# aw_201_clock.net
KiCad netlist of a schematic drawn in EAGLE
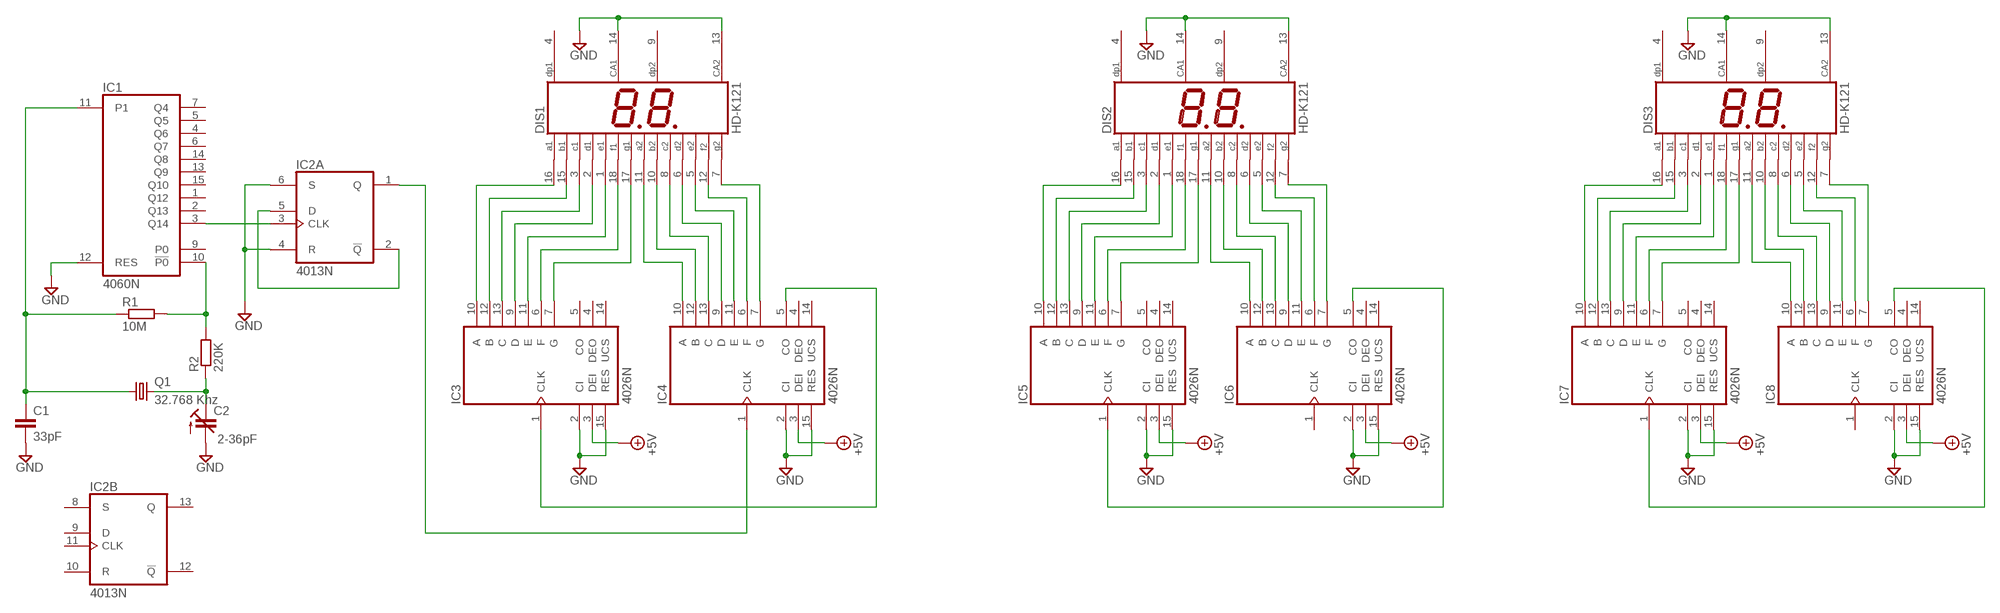
[diagram p0: schematic, sheet 1]

(export (version "E")
  (design (tool "Eeschema 10.0.6"))
  (components
    (comp (ref "C1")
      (value "33pF")
      (footprint "eagle-import:C050-024X044")
      (libsource (lib "eagle-import") (part "C-EU050-024X044"))
    )
    (comp (ref "C2")
      (value "2-36pF")
      (footprint "eagle-import:CTRIM3050.504")
      (libsource (lib "eagle-import") (part "C-TRIMM3050.504"))
    )
    (comp (ref "DIS1")
      (value "HD-K121")
      (footprint "eagle-import:HDSP-R")
      (libsource (lib "eagle-import") (part "HD-K121"))
    )
    (comp (ref "DIS2")
      (value "HD-K121")
      (footprint "eagle-import:HDSP-R")
      (libsource (lib "eagle-import") (part "HD-K121"))
    )
    (comp (ref "DIS3")
      (value "HD-K121")
      (footprint "eagle-import:HDSP-R")
      (libsource (lib "eagle-import") (part "HD-K121"))
    )
    (comp (ref "IC1")
      (value "4060N")
      (footprint "eagle-import:DIL16")
      (libsource (lib "eagle-import") (part "4060N"))
    )
    (comp (ref "IC2")
      (value "4013N")
      (footprint "eagle-import:DIL14")
      (libsource (lib "eagle-import") (part "4013N"))
    )
    (comp (ref "IC3")
      (value "4026N")
      (footprint "eagle-import:DIL16")
      (libsource (lib "eagle-import") (part "4026N"))
    )
    (comp (ref "IC4")
      (value "4026N")
      (footprint "eagle-import:DIL16")
      (libsource (lib "eagle-import") (part "4026N"))
    )
    (comp (ref "IC5")
      (value "4026N")
      (footprint "eagle-import:DIL16")
      (libsource (lib "eagle-import") (part "4026N"))
    )
    (comp (ref "IC6")
      (value "4026N")
      (footprint "eagle-import:DIL16")
      (libsource (lib "eagle-import") (part "4026N"))
    )
    (comp (ref "IC7")
      (value "4026N")
      (footprint "eagle-import:DIL16")
      (libsource (lib "eagle-import") (part "4026N"))
    )
    (comp (ref "IC8")
      (value "4026N")
      (footprint "eagle-import:DIL16")
      (libsource (lib "eagle-import") (part "4026N"))
    )
    (comp (ref "Q1")
      (value "32.768 Khz")
      (footprint "eagle-import:TC26V")
      (libsource (lib "eagle-import") (part "CRYSTALTC26V"))
    )
    (comp (ref "R1")
      (value "10M")
      (footprint "eagle-import:0207_10")
      (libsource (lib "eagle-import") (part "R-EU_0207/10"))
    )
    (comp (ref "R2")
      (value "220K")
      (footprint "eagle-import:0207_10")
      (libsource (lib "eagle-import") (part "R-EU_0207/10"))
    )
  )
  (nets
    (net (code "1") (name "+5V") (class "Default")
      (node (ref "IC3") (pin "3") (pinfunction "DEI_3") (pintype "input"))
      (node (ref "IC4") (pin "3") (pinfunction "DEI_3") (pintype "input"))
      (node (ref "IC5") (pin "3") (pinfunction "DEI_3") (pintype "input"))
      (node (ref "IC6") (pin "3") (pinfunction "DEI_3") (pintype "input"))
      (node (ref "IC7") (pin "3") (pinfunction "DEI_3") (pintype "input"))
      (node (ref "IC8") (pin "3") (pinfunction "DEI_3") (pintype "input"))
    )
    (net (code "2") (name "GND") (class "Default")
      (node (ref "C1") (pin "2") (pinfunction "2_2") (pintype "passive"))
      (node (ref "C2") (pin "2") (pinfunction "A_2") (pintype "passive"))
      (node (ref "DIS1") (pin "13") (pinfunction "CA2_13") (pintype "passive"))
      (node (ref "DIS1") (pin "14") (pinfunction "CA1_14") (pintype "passive"))
      (node (ref "DIS2") (pin "13") (pinfunction "CA2_13") (pintype "passive"))
      (node (ref "DIS2") (pin "14") (pinfunction "CA1_14") (pintype "passive"))
      (node (ref "DIS3") (pin "13") (pinfunction "CA2_13") (pintype "passive"))
      (node (ref "DIS3") (pin "14") (pinfunction "CA1_14") (pintype "passive"))
      (node (ref "IC1") (pin "12") (pinfunction "RES_12") (pintype "input"))
      (node (ref "IC2") (pin "4") (pinfunction "R_4") (pintype "input"))
      (node (ref "IC2") (pin "6") (pinfunction "S_6") (pintype "input"))
      (node (ref "IC3") (pin "15") (pinfunction "RES_15") (pintype "input"))
      (node (ref "IC3") (pin "2") (pinfunction "CI_2") (pintype "input"))
      (node (ref "IC4") (pin "15") (pinfunction "RES_15") (pintype "input"))
      (node (ref "IC4") (pin "2") (pinfunction "CI_2") (pintype "input"))
      (node (ref "IC5") (pin "15") (pinfunction "RES_15") (pintype "input"))
      (node (ref "IC5") (pin "2") (pinfunction "CI_2") (pintype "input"))
      (node (ref "IC6") (pin "15") (pinfunction "RES_15") (pintype "input"))
      (node (ref "IC6") (pin "2") (pinfunction "CI_2") (pintype "input"))
      (node (ref "IC7") (pin "15") (pinfunction "RES_15") (pintype "input"))
      (node (ref "IC7") (pin "2") (pinfunction "CI_2") (pintype "input"))
      (node (ref "IC8") (pin "15") (pinfunction "RES_15") (pintype "input"))
      (node (ref "IC8") (pin "2") (pinfunction "CI_2") (pintype "input"))
    )
    (net (code "3") (name "Net-(C2-E)") (class "Default")
      (node (ref "C2") (pin "1") (pinfunction "E_1") (pintype "passive"))
      (node (ref "Q1") (pin "2") (pinfunction "2_2") (pintype "passive"))
      (node (ref "R2") (pin "1") (pinfunction "1_1") (pintype "passive"))
    )
    (net (code "4") (name "Net-(DIS1-A1)") (class "Default")
      (node (ref "DIS1") (pin "16") (pinfunction "A1_16") (pintype "passive"))
      (node (ref "IC3") (pin "10") (pinfunction "A_10") (pintype "output"))
    )
    (net (code "5") (name "Net-(DIS1-A2)") (class "Default")
      (node (ref "DIS1") (pin "11") (pinfunction "A2_11") (pintype "passive"))
      (node (ref "IC4") (pin "10") (pinfunction "A_10") (pintype "output"))
    )
    (net (code "6") (name "Net-(DIS1-B1)") (class "Default")
      (node (ref "DIS1") (pin "15") (pinfunction "B1_15") (pintype "passive"))
      (node (ref "IC3") (pin "12") (pinfunction "B_12") (pintype "output"))
    )
    (net (code "7") (name "Net-(DIS1-B2)") (class "Default")
      (node (ref "DIS1") (pin "10") (pinfunction "B2_10") (pintype "passive"))
      (node (ref "IC4") (pin "12") (pinfunction "B_12") (pintype "output"))
    )
    (net (code "8") (name "Net-(DIS1-C1)") (class "Default")
      (node (ref "DIS1") (pin "3") (pinfunction "C1_3") (pintype "passive"))
      (node (ref "IC3") (pin "13") (pinfunction "C_13") (pintype "output"))
    )
    (net (code "9") (name "Net-(DIS1-C2)") (class "Default")
      (node (ref "DIS1") (pin "8") (pinfunction "C2_8") (pintype "passive"))
      (node (ref "IC4") (pin "13") (pinfunction "C_13") (pintype "output"))
    )
    (net (code "10") (name "Net-(DIS1-D1)") (class "Default")
      (node (ref "DIS1") (pin "2") (pinfunction "D1_2") (pintype "passive"))
      (node (ref "IC3") (pin "9") (pinfunction "D_9") (pintype "output"))
    )
    (net (code "11") (name "Net-(DIS1-D2)") (class "Default")
      (node (ref "DIS1") (pin "6") (pinfunction "D2_6") (pintype "passive"))
      (node (ref "IC4") (pin "9") (pinfunction "D_9") (pintype "output"))
    )
    (net (code "12") (name "Net-(DIS1-E1)") (class "Default")
      (node (ref "DIS1") (pin "1") (pinfunction "E1_1") (pintype "passive"))
      (node (ref "IC3") (pin "11") (pinfunction "E_11") (pintype "output"))
    )
    (net (code "13") (name "Net-(DIS1-E2)") (class "Default")
      (node (ref "DIS1") (pin "5") (pinfunction "E2_5") (pintype "passive"))
      (node (ref "IC4") (pin "11") (pinfunction "E_11") (pintype "output"))
    )
    (net (code "14") (name "Net-(DIS1-F1)") (class "Default")
      (node (ref "DIS1") (pin "18") (pinfunction "F1_18") (pintype "passive"))
      (node (ref "IC3") (pin "6") (pinfunction "F_6") (pintype "output"))
    )
    (net (code "15") (name "Net-(DIS1-F2)") (class "Default")
      (node (ref "DIS1") (pin "12") (pinfunction "F2_12") (pintype "passive"))
      (node (ref "IC4") (pin "6") (pinfunction "F_6") (pintype "output"))
    )
    (net (code "16") (name "Net-(DIS1-G1)") (class "Default")
      (node (ref "DIS1") (pin "17") (pinfunction "G1_17") (pintype "passive"))
      (node (ref "IC3") (pin "7") (pinfunction "G_7") (pintype "output"))
    )
    (net (code "17") (name "Net-(DIS1-G2)") (class "Default")
      (node (ref "DIS1") (pin "7") (pinfunction "G2_7") (pintype "passive"))
      (node (ref "IC4") (pin "7") (pinfunction "G_7") (pintype "output"))
    )
    (net (code "18") (name "Net-(DIS2-A1)") (class "Default")
      (node (ref "DIS2") (pin "16") (pinfunction "A1_16") (pintype "passive"))
      (node (ref "IC5") (pin "10") (pinfunction "A_10") (pintype "output"))
    )
    (net (code "19") (name "Net-(DIS2-A2)") (class "Default")
      (node (ref "DIS2") (pin "11") (pinfunction "A2_11") (pintype "passive"))
      (node (ref "IC6") (pin "10") (pinfunction "A_10") (pintype "output"))
    )
    (net (code "20") (name "Net-(DIS2-B1)") (class "Default")
      (node (ref "DIS2") (pin "15") (pinfunction "B1_15") (pintype "passive"))
      (node (ref "IC5") (pin "12") (pinfunction "B_12") (pintype "output"))
    )
    (net (code "21") (name "Net-(DIS2-B2)") (class "Default")
      (node (ref "DIS2") (pin "10") (pinfunction "B2_10") (pintype "passive"))
      (node (ref "IC6") (pin "12") (pinfunction "B_12") (pintype "output"))
    )
    (net (code "22") (name "Net-(DIS2-C1)") (class "Default")
      (node (ref "DIS2") (pin "3") (pinfunction "C1_3") (pintype "passive"))
      (node (ref "IC5") (pin "13") (pinfunction "C_13") (pintype "output"))
    )
    (net (code "23") (name "Net-(DIS2-C2)") (class "Default")
      (node (ref "DIS2") (pin "8") (pinfunction "C2_8") (pintype "passive"))
      (node (ref "IC6") (pin "13") (pinfunction "C_13") (pintype "output"))
    )
    (net (code "24") (name "Net-(DIS2-D1)") (class "Default")
      (node (ref "DIS2") (pin "2") (pinfunction "D1_2") (pintype "passive"))
      (node (ref "IC5") (pin "9") (pinfunction "D_9") (pintype "output"))
    )
    (net (code "25") (name "Net-(DIS2-D2)") (class "Default")
      (node (ref "DIS2") (pin "6") (pinfunction "D2_6") (pintype "passive"))
      (node (ref "IC6") (pin "9") (pinfunction "D_9") (pintype "output"))
    )
    (net (code "26") (name "Net-(DIS2-E1)") (class "Default")
      (node (ref "DIS2") (pin "1") (pinfunction "E1_1") (pintype "passive"))
      (node (ref "IC5") (pin "11") (pinfunction "E_11") (pintype "output"))
    )
    (net (code "27") (name "Net-(DIS2-E2)") (class "Default")
      (node (ref "DIS2") (pin "5") (pinfunction "E2_5") (pintype "passive"))
      (node (ref "IC6") (pin "11") (pinfunction "E_11") (pintype "output"))
    )
    (net (code "28") (name "Net-(DIS2-F1)") (class "Default")
      (node (ref "DIS2") (pin "18") (pinfunction "F1_18") (pintype "passive"))
      (node (ref "IC5") (pin "6") (pinfunction "F_6") (pintype "output"))
    )
    (net (code "29") (name "Net-(DIS2-F2)") (class "Default")
      (node (ref "DIS2") (pin "12") (pinfunction "F2_12") (pintype "passive"))
      (node (ref "IC6") (pin "6") (pinfunction "F_6") (pintype "output"))
    )
    (net (code "30") (name "Net-(DIS2-G1)") (class "Default")
      (node (ref "DIS2") (pin "17") (pinfunction "G1_17") (pintype "passive"))
      (node (ref "IC5") (pin "7") (pinfunction "G_7") (pintype "output"))
    )
    (net (code "31") (name "Net-(DIS2-G2)") (class "Default")
      (node (ref "DIS2") (pin "7") (pinfunction "G2_7") (pintype "passive"))
      (node (ref "IC6") (pin "7") (pinfunction "G_7") (pintype "output"))
    )
    (net (code "32") (name "Net-(DIS3-A1)") (class "Default")
      (node (ref "DIS3") (pin "16") (pinfunction "A1_16") (pintype "passive"))
      (node (ref "IC7") (pin "10") (pinfunction "A_10") (pintype "output"))
    )
    (net (code "33") (name "Net-(DIS3-A2)") (class "Default")
      (node (ref "DIS3") (pin "11") (pinfunction "A2_11") (pintype "passive"))
      (node (ref "IC8") (pin "10") (pinfunction "A_10") (pintype "output"))
    )
    (net (code "34") (name "Net-(DIS3-B1)") (class "Default")
      (node (ref "DIS3") (pin "15") (pinfunction "B1_15") (pintype "passive"))
      (node (ref "IC7") (pin "12") (pinfunction "B_12") (pintype "output"))
    )
    (net (code "35") (name "Net-(DIS3-B2)") (class "Default")
      (node (ref "DIS3") (pin "10") (pinfunction "B2_10") (pintype "passive"))
      (node (ref "IC8") (pin "12") (pinfunction "B_12") (pintype "output"))
    )
    (net (code "36") (name "Net-(DIS3-C1)") (class "Default")
      (node (ref "DIS3") (pin "3") (pinfunction "C1_3") (pintype "passive"))
      (node (ref "IC7") (pin "13") (pinfunction "C_13") (pintype "output"))
    )
    (net (code "37") (name "Net-(DIS3-C2)") (class "Default")
      (node (ref "DIS3") (pin "8") (pinfunction "C2_8") (pintype "passive"))
      (node (ref "IC8") (pin "13") (pinfunction "C_13") (pintype "output"))
    )
    (net (code "38") (name "Net-(DIS3-D1)") (class "Default")
      (node (ref "DIS3") (pin "2") (pinfunction "D1_2") (pintype "passive"))
      (node (ref "IC7") (pin "9") (pinfunction "D_9") (pintype "output"))
    )
    (net (code "39") (name "Net-(DIS3-D2)") (class "Default")
      (node (ref "DIS3") (pin "6") (pinfunction "D2_6") (pintype "passive"))
      (node (ref "IC8") (pin "9") (pinfunction "D_9") (pintype "output"))
    )
    (net (code "40") (name "Net-(DIS3-E1)") (class "Default")
      (node (ref "DIS3") (pin "1") (pinfunction "E1_1") (pintype "passive"))
      (node (ref "IC7") (pin "11") (pinfunction "E_11") (pintype "output"))
    )
    (net (code "41") (name "Net-(DIS3-E2)") (class "Default")
      (node (ref "DIS3") (pin "5") (pinfunction "E2_5") (pintype "passive"))
      (node (ref "IC8") (pin "11") (pinfunction "E_11") (pintype "output"))
    )
    (net (code "42") (name "Net-(DIS3-F1)") (class "Default")
      (node (ref "DIS3") (pin "18") (pinfunction "F1_18") (pintype "passive"))
      (node (ref "IC7") (pin "6") (pinfunction "F_6") (pintype "output"))
    )
    (net (code "43") (name "Net-(DIS3-F2)") (class "Default")
      (node (ref "DIS3") (pin "12") (pinfunction "F2_12") (pintype "passive"))
      (node (ref "IC8") (pin "6") (pinfunction "F_6") (pintype "output"))
    )
    (net (code "44") (name "Net-(DIS3-G1)") (class "Default")
      (node (ref "DIS3") (pin "17") (pinfunction "G1_17") (pintype "passive"))
      (node (ref "IC7") (pin "7") (pinfunction "G_7") (pintype "output"))
    )
    (net (code "45") (name "Net-(DIS3-G2)") (class "Default")
      (node (ref "DIS3") (pin "7") (pinfunction "G2_7") (pintype "passive"))
      (node (ref "IC8") (pin "7") (pinfunction "G_7") (pintype "output"))
    )
    (net (code "46") (name "Net-(IC1A-P1)") (class "Default")
      (node (ref "C1") (pin "1") (pinfunction "1_1") (pintype "passive"))
      (node (ref "IC1") (pin "11") (pinfunction "P1_11") (pintype "input"))
      (node (ref "Q1") (pin "1") (pinfunction "1_1") (pintype "passive"))
      (node (ref "R1") (pin "1") (pinfunction "1_1") (pintype "passive"))
    )
    (net (code "47") (name "Net-(IC1A-Q14)") (class "Default")
      (node (ref "IC1") (pin "3") (pinfunction "Q14_3") (pintype "output"))
      (node (ref "IC2") (pin "3") (pinfunction "CLK_3") (pintype "input"))
    )
    (net (code "48") (name "Net-(IC1A-~{P0})") (class "Default")
      (node (ref "IC1") (pin "10") (pinfunction "~{P0}_10") (pintype "output"))
      (node (ref "R1") (pin "2") (pinfunction "2_2") (pintype "passive"))
      (node (ref "R2") (pin "2") (pinfunction "2_2") (pintype "passive"))
    )
    (net (code "49") (name "Net-(IC2A-D)") (class "Default")
      (node (ref "IC2") (pin "2") (pinfunction "~{Q}_2") (pintype "output"))
      (node (ref "IC2") (pin "5") (pinfunction "D_5") (pintype "input"))
    )
    (net (code "50") (name "Net-(IC2A-Q)") (class "Default")
      (node (ref "IC2") (pin "1") (pinfunction "Q_1") (pintype "output"))
      (node (ref "IC4") (pin "1") (pinfunction "CLK_1") (pintype "input"))
    )
    (net (code "51") (name "Net-(IC3A-CLK)") (class "Default")
      (node (ref "IC3") (pin "1") (pinfunction "CLK_1") (pintype "input"))
      (node (ref "IC4") (pin "5") (pinfunction "CO_5") (pintype "output"))
    )
    (net (code "52") (name "Net-(IC5A-CLK)") (class "Default")
      (node (ref "IC5") (pin "1") (pinfunction "CLK_1") (pintype "input"))
      (node (ref "IC6") (pin "5") (pinfunction "CO_5") (pintype "output"))
    )
    (net (code "53") (name "Net-(IC7A-CLK)") (class "Default")
      (node (ref "IC7") (pin "1") (pinfunction "CLK_1") (pintype "input"))
      (node (ref "IC8") (pin "5") (pinfunction "CO_5") (pintype "output"))
    )
    (net (code "54") (name "unconnected-(DIS1-DP1-Pad4)") (class "Default")
      (node (ref "DIS1") (pin "4") (pinfunction "DP1_4") (pintype "passive"))
    )
    (net (code "55") (name "unconnected-(DIS1-DP2-Pad9)") (class "Default")
      (node (ref "DIS1") (pin "9") (pinfunction "DP2_9") (pintype "passive"))
    )
    (net (code "56") (name "unconnected-(DIS2-DP1-Pad4)") (class "Default")
      (node (ref "DIS2") (pin "4") (pinfunction "DP1_4") (pintype "passive"))
    )
    (net (code "57") (name "unconnected-(DIS2-DP2-Pad9)") (class "Default")
      (node (ref "DIS2") (pin "9") (pinfunction "DP2_9") (pintype "passive"))
    )
    (net (code "58") (name "unconnected-(DIS3-DP1-Pad4)") (class "Default")
      (node (ref "DIS3") (pin "4") (pinfunction "DP1_4") (pintype "passive"))
    )
    (net (code "59") (name "unconnected-(DIS3-DP2-Pad9)") (class "Default")
      (node (ref "DIS3") (pin "9") (pinfunction "DP2_9") (pintype "passive"))
    )
    (net (code "60") (name "unconnected-(IC1A-P0-Pad9)") (class "Default")
      (node (ref "IC1") (pin "9") (pinfunction "P0_9") (pintype "output"))
    )
    (net (code "61") (name "unconnected-(IC1A-Q4-Pad7)") (class "Default")
      (node (ref "IC1") (pin "7") (pinfunction "Q4_7") (pintype "output"))
    )
    (net (code "62") (name "unconnected-(IC1A-Q5-Pad5)") (class "Default")
      (node (ref "IC1") (pin "5") (pinfunction "Q5_5") (pintype "output"))
    )
    (net (code "63") (name "unconnected-(IC1A-Q6-Pad4)") (class "Default")
      (node (ref "IC1") (pin "4") (pinfunction "Q6_4") (pintype "output"))
    )
    (net (code "64") (name "unconnected-(IC1A-Q7-Pad6)") (class "Default")
      (node (ref "IC1") (pin "6") (pinfunction "Q7_6") (pintype "output"))
    )
    (net (code "65") (name "unconnected-(IC1A-Q8-Pad14)") (class "Default")
      (node (ref "IC1") (pin "14") (pinfunction "Q8_14") (pintype "output"))
    )
    (net (code "66") (name "unconnected-(IC1A-Q9-Pad13)") (class "Default")
      (node (ref "IC1") (pin "13") (pinfunction "Q9_13") (pintype "output"))
    )
    (net (code "67") (name "unconnected-(IC1A-Q10-Pad15)") (class "Default")
      (node (ref "IC1") (pin "15") (pinfunction "Q10_15") (pintype "output"))
    )
    (net (code "68") (name "unconnected-(IC1A-Q12-Pad1)") (class "Default")
      (node (ref "IC1") (pin "1") (pinfunction "Q12_1") (pintype "output"))
    )
    (net (code "69") (name "unconnected-(IC1A-Q13-Pad2)") (class "Default")
      (node (ref "IC1") (pin "2") (pinfunction "Q13_2") (pintype "output"))
    )
    (net (code "70") (name "unconnected-(IC2B-CLK-Pad11)") (class "Default")
      (node (ref "IC2") (pin "11") (pinfunction "CLK_11") (pintype "input"))
    )
    (net (code "71") (name "unconnected-(IC2B-D-Pad9)") (class "Default")
      (node (ref "IC2") (pin "9") (pinfunction "D_9") (pintype "input"))
    )
    (net (code "72") (name "unconnected-(IC2B-Q-Pad13)") (class "Default")
      (node (ref "IC2") (pin "13") (pinfunction "Q_13") (pintype "output"))
    )
    (net (code "73") (name "unconnected-(IC2B-R-Pad10)") (class "Default")
      (node (ref "IC2") (pin "10") (pinfunction "R_10") (pintype "input"))
    )
    (net (code "74") (name "unconnected-(IC2B-S-Pad8)") (class "Default")
      (node (ref "IC2") (pin "8") (pinfunction "S_8") (pintype "input"))
    )
    (net (code "75") (name "unconnected-(IC2B-~{Q}-Pad12)") (class "Default")
      (node (ref "IC2") (pin "12") (pinfunction "~{Q}_12") (pintype "output"))
    )
    (net (code "76") (name "unconnected-(IC3A-CO-Pad5)") (class "Default")
      (node (ref "IC3") (pin "5") (pinfunction "CO_5") (pintype "output"))
    )
    (net (code "77") (name "unconnected-(IC3A-DEO-Pad4)") (class "Default")
      (node (ref "IC3") (pin "4") (pinfunction "DEO_4") (pintype "output"))
    )
    (net (code "78") (name "unconnected-(IC3A-UCS-Pad14)") (class "Default")
      (node (ref "IC3") (pin "14") (pinfunction "UCS_14") (pintype "output"))
    )
    (net (code "79") (name "unconnected-(IC4A-DEO-Pad4)") (class "Default")
      (node (ref "IC4") (pin "4") (pinfunction "DEO_4") (pintype "output"))
    )
    (net (code "80") (name "unconnected-(IC4A-UCS-Pad14)") (class "Default")
      (node (ref "IC4") (pin "14") (pinfunction "UCS_14") (pintype "output"))
    )
    (net (code "81") (name "unconnected-(IC5A-CO-Pad5)") (class "Default")
      (node (ref "IC5") (pin "5") (pinfunction "CO_5") (pintype "output"))
    )
    (net (code "82") (name "unconnected-(IC5A-DEO-Pad4)") (class "Default")
      (node (ref "IC5") (pin "4") (pinfunction "DEO_4") (pintype "output"))
    )
    (net (code "83") (name "unconnected-(IC5A-UCS-Pad14)") (class "Default")
      (node (ref "IC5") (pin "14") (pinfunction "UCS_14") (pintype "output"))
    )
    (net (code "84") (name "unconnected-(IC6A-CLK-Pad1)") (class "Default")
      (node (ref "IC6") (pin "1") (pinfunction "CLK_1") (pintype "input"))
    )
    (net (code "85") (name "unconnected-(IC6A-DEO-Pad4)") (class "Default")
      (node (ref "IC6") (pin "4") (pinfunction "DEO_4") (pintype "output"))
    )
    (net (code "86") (name "unconnected-(IC6A-UCS-Pad14)") (class "Default")
      (node (ref "IC6") (pin "14") (pinfunction "UCS_14") (pintype "output"))
    )
    (net (code "87") (name "unconnected-(IC7A-CO-Pad5)") (class "Default")
      (node (ref "IC7") (pin "5") (pinfunction "CO_5") (pintype "output"))
    )
    (net (code "88") (name "unconnected-(IC7A-DEO-Pad4)") (class "Default")
      (node (ref "IC7") (pin "4") (pinfunction "DEO_4") (pintype "output"))
    )
    (net (code "89") (name "unconnected-(IC7A-UCS-Pad14)") (class "Default")
      (node (ref "IC7") (pin "14") (pinfunction "UCS_14") (pintype "output"))
    )
    (net (code "90") (name "unconnected-(IC8A-CLK-Pad1)") (class "Default")
      (node (ref "IC8") (pin "1") (pinfunction "CLK_1") (pintype "input"))
    )
    (net (code "91") (name "unconnected-(IC8A-DEO-Pad4)") (class "Default")
      (node (ref "IC8") (pin "4") (pinfunction "DEO_4") (pintype "output"))
    )
    (net (code "92") (name "unconnected-(IC8A-UCS-Pad14)") (class "Default")
      (node (ref "IC8") (pin "14") (pinfunction "UCS_14") (pintype "output"))
    )
  )
)
